# Sheet1.net
KiCad netlist of a schematic drawn in Altium Designer
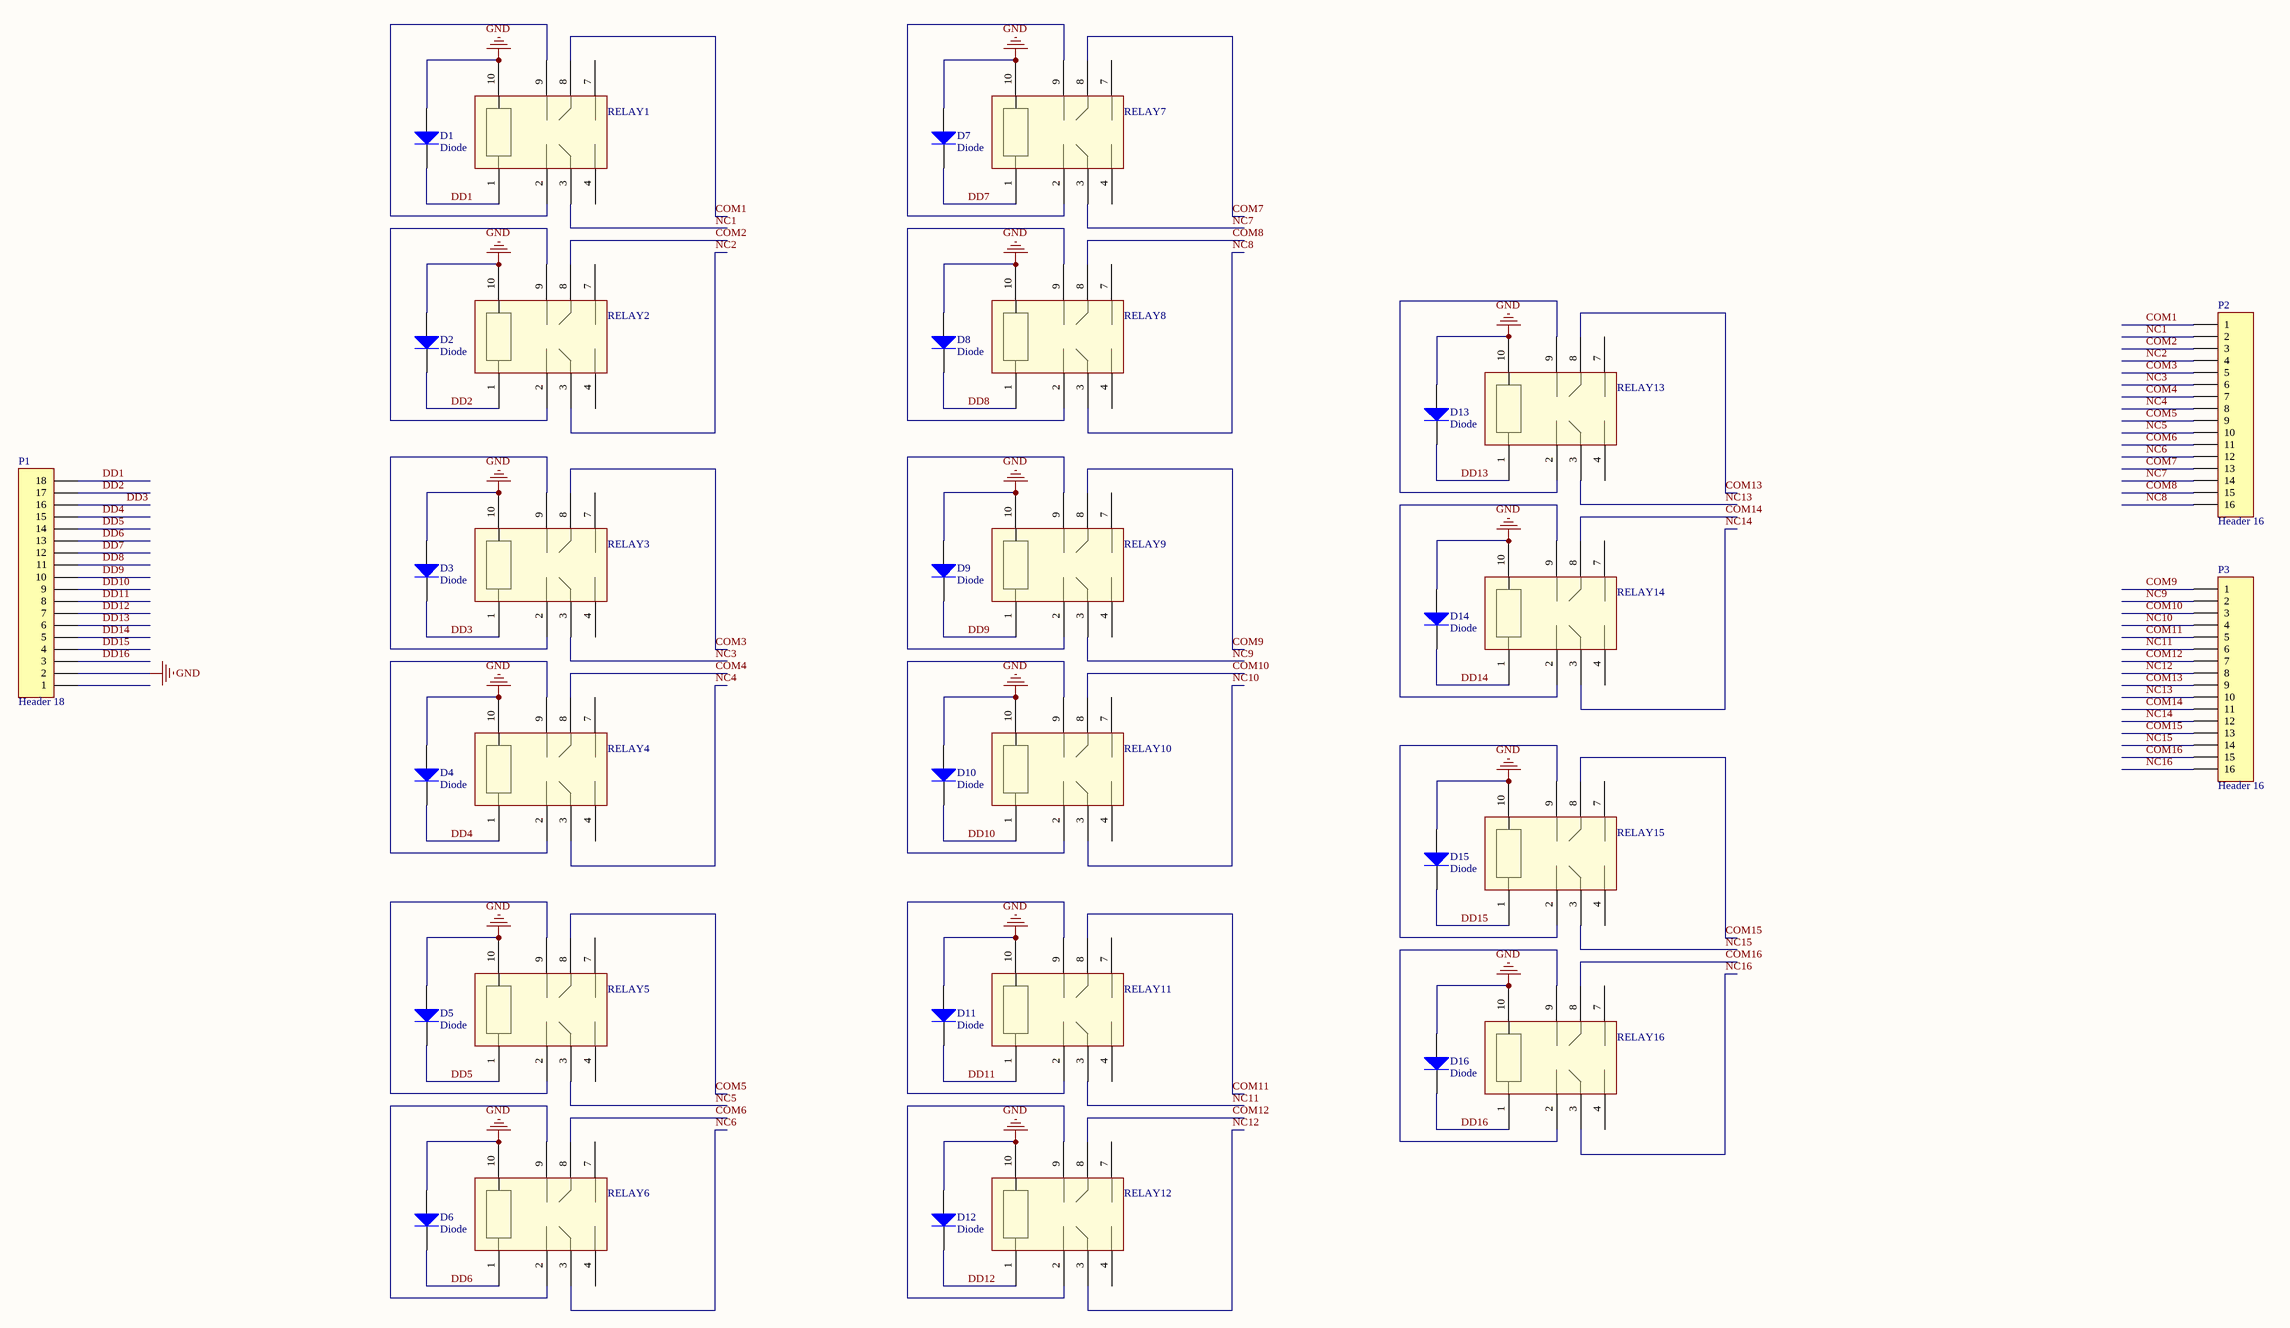
[diagram p0: Sheet1.SchDoc]

(export (version "E")
  (design (tool "Eeschema 10.0.6"))
  (components
    (comp (ref "D1")
      (value "Diode")
      (footprint "SMB")
      (description "Default Diode")
      (fields (field (name "PUBLISHER") "Altium Limited"))
      (libsource (lib "Miscellaneous Devices") (part "Diode"))
    )
    (comp (ref "D2")
      (value "Diode")
      (footprint "SMB")
      (description "Default Diode")
      (fields (field (name "PUBLISHER") "Altium Limited"))
      (libsource (lib "Miscellaneous Devices") (part "Diode"))
    )
    (comp (ref "D3")
      (value "Diode")
      (footprint "SMB")
      (description "Default Diode")
      (fields (field (name "PUBLISHER") "Altium Limited"))
      (libsource (lib "Miscellaneous Devices") (part "Diode"))
    )
    (comp (ref "D4")
      (value "Diode")
      (footprint "SMB")
      (description "Default Diode")
      (fields (field (name "PUBLISHER") "Altium Limited"))
      (libsource (lib "Miscellaneous Devices") (part "Diode"))
    )
    (comp (ref "D5")
      (value "Diode")
      (footprint "SMB")
      (description "Default Diode")
      (fields (field (name "PUBLISHER") "Altium Limited"))
      (libsource (lib "Miscellaneous Devices") (part "Diode"))
    )
    (comp (ref "D6")
      (value "Diode")
      (footprint "SMB")
      (description "Default Diode")
      (fields (field (name "PUBLISHER") "Altium Limited"))
      (libsource (lib "Miscellaneous Devices") (part "Diode"))
    )
    (comp (ref "D7")
      (value "Diode")
      (footprint "SMB")
      (description "Default Diode")
      (fields (field (name "PUBLISHER") "Altium Limited"))
      (libsource (lib "Miscellaneous Devices") (part "Diode"))
    )
    (comp (ref "D8")
      (value "Diode")
      (footprint "SMB")
      (description "Default Diode")
      (fields (field (name "PUBLISHER") "Altium Limited"))
      (libsource (lib "Miscellaneous Devices") (part "Diode"))
    )
    (comp (ref "D9")
      (value "Diode")
      (footprint "SMB")
      (description "Default Diode")
      (fields (field (name "PUBLISHER") "Altium Limited"))
      (libsource (lib "Miscellaneous Devices") (part "Diode"))
    )
    (comp (ref "D10")
      (value "Diode")
      (footprint "SMB")
      (description "Default Diode")
      (fields (field (name "PUBLISHER") "Altium Limited"))
      (libsource (lib "Miscellaneous Devices") (part "Diode"))
    )
    (comp (ref "D11")
      (value "Diode")
      (footprint "SMB")
      (description "Default Diode")
      (fields (field (name "PUBLISHER") "Altium Limited"))
      (libsource (lib "Miscellaneous Devices") (part "Diode"))
    )
    (comp (ref "D12")
      (value "Diode")
      (footprint "SMB")
      (description "Default Diode")
      (fields (field (name "PUBLISHER") "Altium Limited"))
      (libsource (lib "Miscellaneous Devices") (part "Diode"))
    )
    (comp (ref "D13")
      (value "Diode")
      (footprint "SMB")
      (description "Default Diode")
      (fields (field (name "PUBLISHER") "Altium Limited"))
      (libsource (lib "Miscellaneous Devices") (part "Diode"))
    )
    (comp (ref "D14")
      (value "Diode")
      (footprint "SMB")
      (description "Default Diode")
      (fields (field (name "PUBLISHER") "Altium Limited"))
      (libsource (lib "Miscellaneous Devices") (part "Diode"))
    )
    (comp (ref "D15")
      (value "Diode")
      (footprint "SMB")
      (description "Default Diode")
      (fields (field (name "PUBLISHER") "Altium Limited"))
      (libsource (lib "Miscellaneous Devices") (part "Diode"))
    )
    (comp (ref "D16")
      (value "Diode")
      (footprint "SMB")
      (description "Default Diode")
      (fields (field (name "PUBLISHER") "Altium Limited"))
      (libsource (lib "Miscellaneous Devices") (part "Diode"))
    )
    (comp (ref "P1")
      (value "Header 18")
      (footprint "CON 18")
      (description "Header, 18-Pin")
      (fields (field (name "PUBLISHER") "Altium Limited"))
      (libsource (lib "Miscellaneous Connectors") (part "Header 18"))
    )
    (comp (ref "P2")
      (value "Header 16")
      (footprint "CON 16")
      (description "Header, 16-Pin")
      (fields (field (name "PUBLISHER") "Altium Limited"))
      (libsource (lib "Miscellaneous Connectors") (part "Header 16"))
    )
    (comp (ref "P3")
      (value "Header 16")
      (footprint "CON 16")
      (description "Header, 16-Pin")
      (fields (field (name "PUBLISHER") "Altium Limited"))
      (libsource (lib "Miscellaneous Connectors") (part "Header 16"))
    )
    (comp (ref "RELAY1")
      (value "OMRON RELAY")
      (footprint "G6H-2")
      (libsource (lib "dung_maker_2018") (part "OMRON G6H-2"))
    )
    (comp (ref "RELAY2")
      (value "OMRON RELAY")
      (footprint "G6H-2")
      (libsource (lib "dung_maker_2018") (part "OMRON G6H-2"))
    )
    (comp (ref "RELAY3")
      (value "OMRON RELAY")
      (footprint "G6H-2")
      (libsource (lib "dung_maker_2018") (part "OMRON G6H-2"))
    )
    (comp (ref "RELAY4")
      (value "OMRON RELAY")
      (footprint "G6H-2")
      (libsource (lib "dung_maker_2018") (part "OMRON G6H-2"))
    )
    (comp (ref "RELAY5")
      (value "OMRON RELAY")
      (footprint "G6H-2")
      (libsource (lib "dung_maker_2018") (part "OMRON G6H-2"))
    )
    (comp (ref "RELAY6")
      (value "OMRON RELAY")
      (footprint "G6H-2")
      (libsource (lib "dung_maker_2018") (part "OMRON G6H-2"))
    )
    (comp (ref "RELAY7")
      (value "OMRON RELAY")
      (footprint "G6H-2")
      (libsource (lib "dung_maker_2018") (part "OMRON G6H-2"))
    )
    (comp (ref "RELAY8")
      (value "OMRON RELAY")
      (footprint "G6H-2")
      (libsource (lib "dung_maker_2018") (part "OMRON G6H-2"))
    )
    (comp (ref "RELAY9")
      (value "OMRON RELAY")
      (footprint "G6H-2")
      (libsource (lib "dung_maker_2018") (part "OMRON G6H-2"))
    )
    (comp (ref "RELAY10")
      (value "OMRON RELAY")
      (footprint "G6H-2")
      (libsource (lib "dung_maker_2018") (part "OMRON G6H-2"))
    )
    (comp (ref "RELAY11")
      (value "OMRON RELAY")
      (footprint "G6H-2")
      (libsource (lib "dung_maker_2018") (part "OMRON G6H-2"))
    )
    (comp (ref "RELAY12")
      (value "OMRON RELAY")
      (footprint "G6H-2")
      (libsource (lib "dung_maker_2018") (part "OMRON G6H-2"))
    )
    (comp (ref "RELAY13")
      (value "OMRON RELAY")
      (footprint "G6H-2")
      (libsource (lib "dung_maker_2018") (part "OMRON G6H-2"))
    )
    (comp (ref "RELAY14")
      (value "OMRON RELAY")
      (footprint "G6H-2")
      (libsource (lib "dung_maker_2018") (part "OMRON G6H-2"))
    )
    (comp (ref "RELAY15")
      (value "OMRON RELAY")
      (footprint "G6H-2")
      (libsource (lib "dung_maker_2018") (part "OMRON G6H-2"))
    )
    (comp (ref "RELAY16")
      (value "OMRON RELAY")
      (footprint "G6H-2")
      (libsource (lib "dung_maker_2018") (part "OMRON G6H-2"))
    )
  )
  (nets
    (net (code "1") (name "/COM1") (class "Default")
      (node (ref "P2") (pin "1") (pinfunction "1_1") (pintype "passive"))
      (node (ref "RELAY1") (pin "8") (pinfunction "8_8") (pintype "passive"))
    )
    (net (code "2") (name "/COM2") (class "Default")
      (node (ref "P2") (pin "3") (pinfunction "3_3") (pintype "passive"))
      (node (ref "RELAY2") (pin "8") (pinfunction "8_8") (pintype "passive"))
    )
    (net (code "3") (name "/COM3") (class "Default")
      (node (ref "P2") (pin "5") (pinfunction "5_5") (pintype "passive"))
      (node (ref "RELAY3") (pin "8") (pinfunction "8_8") (pintype "passive"))
    )
    (net (code "4") (name "/COM4") (class "Default")
      (node (ref "P2") (pin "7") (pinfunction "7_7") (pintype "passive"))
      (node (ref "RELAY4") (pin "8") (pinfunction "8_8") (pintype "passive"))
    )
    (net (code "5") (name "/COM5") (class "Default")
      (node (ref "P2") (pin "9") (pinfunction "9_9") (pintype "passive"))
      (node (ref "RELAY5") (pin "8") (pinfunction "8_8") (pintype "passive"))
    )
    (net (code "6") (name "/COM6") (class "Default")
      (node (ref "P2") (pin "11") (pinfunction "11_11") (pintype "passive"))
      (node (ref "RELAY6") (pin "8") (pinfunction "8_8") (pintype "passive"))
    )
    (net (code "7") (name "/COM7") (class "Default")
      (node (ref "P2") (pin "13") (pinfunction "13_13") (pintype "passive"))
      (node (ref "RELAY7") (pin "8") (pinfunction "8_8") (pintype "passive"))
    )
    (net (code "8") (name "/COM8") (class "Default")
      (node (ref "P2") (pin "15") (pinfunction "15_15") (pintype "passive"))
      (node (ref "RELAY8") (pin "8") (pinfunction "8_8") (pintype "passive"))
    )
    (net (code "9") (name "/COM9") (class "Default")
      (node (ref "P3") (pin "1") (pinfunction "1_1") (pintype "passive"))
      (node (ref "RELAY9") (pin "8") (pinfunction "8_8") (pintype "passive"))
    )
    (net (code "10") (name "/COM10") (class "Default")
      (node (ref "P3") (pin "3") (pinfunction "3_3") (pintype "passive"))
      (node (ref "RELAY10") (pin "8") (pinfunction "8_8") (pintype "passive"))
    )
    (net (code "11") (name "/COM11") (class "Default")
      (node (ref "P3") (pin "5") (pinfunction "5_5") (pintype "passive"))
      (node (ref "RELAY11") (pin "8") (pinfunction "8_8") (pintype "passive"))
    )
    (net (code "12") (name "/COM12") (class "Default")
      (node (ref "P3") (pin "7") (pinfunction "7_7") (pintype "passive"))
      (node (ref "RELAY12") (pin "8") (pinfunction "8_8") (pintype "passive"))
    )
    (net (code "13") (name "/COM13") (class "Default")
      (node (ref "P3") (pin "9") (pinfunction "9_9") (pintype "passive"))
      (node (ref "RELAY13") (pin "8") (pinfunction "8_8") (pintype "passive"))
    )
    (net (code "14") (name "/COM14") (class "Default")
      (node (ref "P3") (pin "11") (pinfunction "11_11") (pintype "passive"))
      (node (ref "RELAY14") (pin "8") (pinfunction "8_8") (pintype "passive"))
    )
    (net (code "15") (name "/COM15") (class "Default")
      (node (ref "P3") (pin "13") (pinfunction "13_13") (pintype "passive"))
      (node (ref "RELAY15") (pin "8") (pinfunction "8_8") (pintype "passive"))
    )
    (net (code "16") (name "/COM16") (class "Default")
      (node (ref "P3") (pin "15") (pinfunction "15_15") (pintype "passive"))
      (node (ref "RELAY16") (pin "8") (pinfunction "8_8") (pintype "passive"))
    )
    (net (code "17") (name "/DD1") (class "Default")
      (node (ref "D1") (pin "2") (pinfunction "K_2") (pintype "passive"))
      (node (ref "P1") (pin "18") (pinfunction "18_18") (pintype "passive"))
      (node (ref "RELAY1") (pin "1") (pinfunction "1_1") (pintype "passive"))
    )
    (net (code "18") (name "/DD2") (class "Default")
      (node (ref "D2") (pin "2") (pinfunction "K_2") (pintype "passive"))
      (node (ref "P1") (pin "17") (pinfunction "17_17") (pintype "passive"))
      (node (ref "RELAY2") (pin "1") (pinfunction "1_1") (pintype "passive"))
    )
    (net (code "19") (name "/DD3") (class "Default")
      (node (ref "D3") (pin "2") (pinfunction "K_2") (pintype "passive"))
      (node (ref "P1") (pin "16") (pinfunction "16_16") (pintype "passive"))
      (node (ref "RELAY3") (pin "1") (pinfunction "1_1") (pintype "passive"))
    )
    (net (code "20") (name "/DD4") (class "Default")
      (node (ref "D4") (pin "2") (pinfunction "K_2") (pintype "passive"))
      (node (ref "P1") (pin "15") (pinfunction "15_15") (pintype "passive"))
      (node (ref "RELAY4") (pin "1") (pinfunction "1_1") (pintype "passive"))
    )
    (net (code "21") (name "/DD5") (class "Default")
      (node (ref "D5") (pin "2") (pinfunction "K_2") (pintype "passive"))
      (node (ref "P1") (pin "14") (pinfunction "14_14") (pintype "passive"))
      (node (ref "RELAY5") (pin "1") (pinfunction "1_1") (pintype "passive"))
    )
    (net (code "22") (name "/DD6") (class "Default")
      (node (ref "D6") (pin "2") (pinfunction "K_2") (pintype "passive"))
      (node (ref "P1") (pin "13") (pinfunction "13_13") (pintype "passive"))
      (node (ref "RELAY6") (pin "1") (pinfunction "1_1") (pintype "passive"))
    )
    (net (code "23") (name "/DD7") (class "Default")
      (node (ref "D7") (pin "2") (pinfunction "K_2") (pintype "passive"))
      (node (ref "P1") (pin "12") (pinfunction "12_12") (pintype "passive"))
      (node (ref "RELAY7") (pin "1") (pinfunction "1_1") (pintype "passive"))
    )
    (net (code "24") (name "/DD8") (class "Default")
      (node (ref "D8") (pin "2") (pinfunction "K_2") (pintype "passive"))
      (node (ref "P1") (pin "11") (pinfunction "11_11") (pintype "passive"))
      (node (ref "RELAY8") (pin "1") (pinfunction "1_1") (pintype "passive"))
    )
    (net (code "25") (name "/DD9") (class "Default")
      (node (ref "D9") (pin "2") (pinfunction "K_2") (pintype "passive"))
      (node (ref "P1") (pin "10") (pinfunction "10_10") (pintype "passive"))
      (node (ref "RELAY9") (pin "1") (pinfunction "1_1") (pintype "passive"))
    )
    (net (code "26") (name "/DD10") (class "Default")
      (node (ref "D10") (pin "2") (pinfunction "K_2") (pintype "passive"))
      (node (ref "P1") (pin "9") (pinfunction "9_9") (pintype "passive"))
      (node (ref "RELAY10") (pin "1") (pinfunction "1_1") (pintype "passive"))
    )
    (net (code "27") (name "/DD11") (class "Default")
      (node (ref "D11") (pin "2") (pinfunction "K_2") (pintype "passive"))
      (node (ref "P1") (pin "8") (pinfunction "8_8") (pintype "passive"))
      (node (ref "RELAY11") (pin "1") (pinfunction "1_1") (pintype "passive"))
    )
    (net (code "28") (name "/DD12") (class "Default")
      (node (ref "D12") (pin "2") (pinfunction "K_2") (pintype "passive"))
      (node (ref "P1") (pin "7") (pinfunction "7_7") (pintype "passive"))
      (node (ref "RELAY12") (pin "1") (pinfunction "1_1") (pintype "passive"))
    )
    (net (code "29") (name "/DD13") (class "Default")
      (node (ref "D13") (pin "2") (pinfunction "K_2") (pintype "passive"))
      (node (ref "P1") (pin "6") (pinfunction "6_6") (pintype "passive"))
      (node (ref "RELAY13") (pin "1") (pinfunction "1_1") (pintype "passive"))
    )
    (net (code "30") (name "/DD14") (class "Default")
      (node (ref "D14") (pin "2") (pinfunction "K_2") (pintype "passive"))
      (node (ref "P1") (pin "5") (pinfunction "5_5") (pintype "passive"))
      (node (ref "RELAY14") (pin "1") (pinfunction "1_1") (pintype "passive"))
    )
    (net (code "31") (name "/DD15") (class "Default")
      (node (ref "D15") (pin "2") (pinfunction "K_2") (pintype "passive"))
      (node (ref "P1") (pin "4") (pinfunction "4_4") (pintype "passive"))
      (node (ref "RELAY15") (pin "1") (pinfunction "1_1") (pintype "passive"))
    )
    (net (code "32") (name "/DD16") (class "Default")
      (node (ref "D16") (pin "2") (pinfunction "K_2") (pintype "passive"))
      (node (ref "P1") (pin "3") (pinfunction "3_3") (pintype "passive"))
      (node (ref "RELAY16") (pin "1") (pinfunction "1_1") (pintype "passive"))
    )
    (net (code "33") (name "/NC1") (class "Default")
      (node (ref "P2") (pin "2") (pinfunction "2_2") (pintype "passive"))
      (node (ref "RELAY1") (pin "3") (pinfunction "3_3") (pintype "passive"))
    )
    (net (code "34") (name "/NC2") (class "Default")
      (node (ref "P2") (pin "4") (pinfunction "4_4") (pintype "passive"))
      (node (ref "RELAY2") (pin "3") (pinfunction "3_3") (pintype "passive"))
    )
    (net (code "35") (name "/NC3") (class "Default")
      (node (ref "P2") (pin "6") (pinfunction "6_6") (pintype "passive"))
      (node (ref "RELAY3") (pin "3") (pinfunction "3_3") (pintype "passive"))
    )
    (net (code "36") (name "/NC4") (class "Default")
      (node (ref "P2") (pin "8") (pinfunction "8_8") (pintype "passive"))
      (node (ref "RELAY4") (pin "3") (pinfunction "3_3") (pintype "passive"))
    )
    (net (code "37") (name "/NC5") (class "Default")
      (node (ref "P2") (pin "10") (pinfunction "10_10") (pintype "passive"))
      (node (ref "RELAY5") (pin "3") (pinfunction "3_3") (pintype "passive"))
    )
    (net (code "38") (name "/NC6") (class "Default")
      (node (ref "P2") (pin "12") (pinfunction "12_12") (pintype "passive"))
      (node (ref "RELAY6") (pin "3") (pinfunction "3_3") (pintype "passive"))
    )
    (net (code "39") (name "/NC7") (class "Default")
      (node (ref "P2") (pin "14") (pinfunction "14_14") (pintype "passive"))
      (node (ref "RELAY7") (pin "3") (pinfunction "3_3") (pintype "passive"))
    )
    (net (code "40") (name "/NC8") (class "Default")
      (node (ref "P2") (pin "16") (pinfunction "16_16") (pintype "passive"))
      (node (ref "RELAY8") (pin "3") (pinfunction "3_3") (pintype "passive"))
    )
    (net (code "41") (name "/NC9") (class "Default")
      (node (ref "P3") (pin "2") (pinfunction "2_2") (pintype "passive"))
      (node (ref "RELAY9") (pin "3") (pinfunction "3_3") (pintype "passive"))
    )
    (net (code "42") (name "/NC10") (class "Default")
      (node (ref "P3") (pin "4") (pinfunction "4_4") (pintype "passive"))
      (node (ref "RELAY10") (pin "3") (pinfunction "3_3") (pintype "passive"))
    )
    (net (code "43") (name "/NC11") (class "Default")
      (node (ref "P3") (pin "6") (pinfunction "6_6") (pintype "passive"))
      (node (ref "RELAY11") (pin "3") (pinfunction "3_3") (pintype "passive"))
    )
    (net (code "44") (name "/NC12") (class "Default")
      (node (ref "P3") (pin "8") (pinfunction "8_8") (pintype "passive"))
      (node (ref "RELAY12") (pin "3") (pinfunction "3_3") (pintype "passive"))
    )
    (net (code "45") (name "/NC13") (class "Default")
      (node (ref "P3") (pin "10") (pinfunction "10_10") (pintype "passive"))
      (node (ref "RELAY13") (pin "3") (pinfunction "3_3") (pintype "passive"))
    )
    (net (code "46") (name "/NC14") (class "Default")
      (node (ref "P3") (pin "12") (pinfunction "12_12") (pintype "passive"))
      (node (ref "RELAY14") (pin "3") (pinfunction "3_3") (pintype "passive"))
    )
    (net (code "47") (name "/NC15") (class "Default")
      (node (ref "P3") (pin "14") (pinfunction "14_14") (pintype "passive"))
      (node (ref "RELAY15") (pin "3") (pinfunction "3_3") (pintype "passive"))
    )
    (net (code "48") (name "/NC16") (class "Default")
      (node (ref "P3") (pin "16") (pinfunction "16_16") (pintype "passive"))
      (node (ref "RELAY16") (pin "3") (pinfunction "3_3") (pintype "passive"))
    )
    (net (code "49") (name "GND") (class "Default")
      (node (ref "D1") (pin "1") (pinfunction "A_1") (pintype "passive"))
      (node (ref "D10") (pin "1") (pinfunction "A_1") (pintype "passive"))
      (node (ref "D11") (pin "1") (pinfunction "A_1") (pintype "passive"))
      (node (ref "D12") (pin "1") (pinfunction "A_1") (pintype "passive"))
      (node (ref "D13") (pin "1") (pinfunction "A_1") (pintype "passive"))
      (node (ref "D14") (pin "1") (pinfunction "A_1") (pintype "passive"))
      (node (ref "D15") (pin "1") (pinfunction "A_1") (pintype "passive"))
      (node (ref "D16") (pin "1") (pinfunction "A_1") (pintype "passive"))
      (node (ref "D2") (pin "1") (pinfunction "A_1") (pintype "passive"))
      (node (ref "D3") (pin "1") (pinfunction "A_1") (pintype "passive"))
      (node (ref "D4") (pin "1") (pinfunction "A_1") (pintype "passive"))
      (node (ref "D5") (pin "1") (pinfunction "A_1") (pintype "passive"))
      (node (ref "D6") (pin "1") (pinfunction "A_1") (pintype "passive"))
      (node (ref "D7") (pin "1") (pinfunction "A_1") (pintype "passive"))
      (node (ref "D8") (pin "1") (pinfunction "A_1") (pintype "passive"))
      (node (ref "D9") (pin "1") (pinfunction "A_1") (pintype "passive"))
      (node (ref "P1") (pin "2") (pinfunction "2_2") (pintype "passive"))
      (node (ref "RELAY1") (pin "10") (pinfunction "10_10") (pintype "passive"))
      (node (ref "RELAY10") (pin "10") (pinfunction "10_10") (pintype "passive"))
      (node (ref "RELAY11") (pin "10") (pinfunction "10_10") (pintype "passive"))
      (node (ref "RELAY12") (pin "10") (pinfunction "10_10") (pintype "passive"))
      (node (ref "RELAY13") (pin "10") (pinfunction "10_10") (pintype "passive"))
      (node (ref "RELAY14") (pin "10") (pinfunction "10_10") (pintype "passive"))
      (node (ref "RELAY15") (pin "10") (pinfunction "10_10") (pintype "passive"))
      (node (ref "RELAY16") (pin "10") (pinfunction "10_10") (pintype "passive"))
      (node (ref "RELAY2") (pin "10") (pinfunction "10_10") (pintype "passive"))
      (node (ref "RELAY3") (pin "10") (pinfunction "10_10") (pintype "passive"))
      (node (ref "RELAY4") (pin "10") (pinfunction "10_10") (pintype "passive"))
      (node (ref "RELAY5") (pin "10") (pinfunction "10_10") (pintype "passive"))
      (node (ref "RELAY6") (pin "10") (pinfunction "10_10") (pintype "passive"))
      (node (ref "RELAY7") (pin "10") (pinfunction "10_10") (pintype "passive"))
      (node (ref "RELAY8") (pin "10") (pinfunction "10_10") (pintype "passive"))
      (node (ref "RELAY9") (pin "10") (pinfunction "10_10") (pintype "passive"))
    )
    (net (code "50") (name "Net-(RELAY1-Pad2)") (class "Default")
      (node (ref "RELAY1") (pin "2") (pinfunction "2_2") (pintype "passive"))
      (node (ref "RELAY1") (pin "9") (pinfunction "9_9") (pintype "passive"))
    )
    (net (code "51") (name "Net-(RELAY2-Pad2)") (class "Default")
      (node (ref "RELAY2") (pin "2") (pinfunction "2_2") (pintype "passive"))
      (node (ref "RELAY2") (pin "9") (pinfunction "9_9") (pintype "passive"))
    )
    (net (code "52") (name "Net-(RELAY3-Pad2)") (class "Default")
      (node (ref "RELAY3") (pin "2") (pinfunction "2_2") (pintype "passive"))
      (node (ref "RELAY3") (pin "9") (pinfunction "9_9") (pintype "passive"))
    )
    (net (code "53") (name "Net-(RELAY4-Pad2)") (class "Default")
      (node (ref "RELAY4") (pin "2") (pinfunction "2_2") (pintype "passive"))
      (node (ref "RELAY4") (pin "9") (pinfunction "9_9") (pintype "passive"))
    )
    (net (code "54") (name "Net-(RELAY5-Pad2)") (class "Default")
      (node (ref "RELAY5") (pin "2") (pinfunction "2_2") (pintype "passive"))
      (node (ref "RELAY5") (pin "9") (pinfunction "9_9") (pintype "passive"))
    )
    (net (code "55") (name "Net-(RELAY6-Pad2)") (class "Default")
      (node (ref "RELAY6") (pin "2") (pinfunction "2_2") (pintype "passive"))
      (node (ref "RELAY6") (pin "9") (pinfunction "9_9") (pintype "passive"))
    )
    (net (code "56") (name "Net-(RELAY7-Pad2)") (class "Default")
      (node (ref "RELAY7") (pin "2") (pinfunction "2_2") (pintype "passive"))
      (node (ref "RELAY7") (pin "9") (pinfunction "9_9") (pintype "passive"))
    )
    (net (code "57") (name "Net-(RELAY8-Pad2)") (class "Default")
      (node (ref "RELAY8") (pin "2") (pinfunction "2_2") (pintype "passive"))
      (node (ref "RELAY8") (pin "9") (pinfunction "9_9") (pintype "passive"))
    )
    (net (code "58") (name "Net-(RELAY9-Pad2)") (class "Default")
      (node (ref "RELAY9") (pin "2") (pinfunction "2_2") (pintype "passive"))
      (node (ref "RELAY9") (pin "9") (pinfunction "9_9") (pintype "passive"))
    )
    (net (code "59") (name "Net-(RELAY10-Pad2)") (class "Default")
      (node (ref "RELAY10") (pin "2") (pinfunction "2_2") (pintype "passive"))
      (node (ref "RELAY10") (pin "9") (pinfunction "9_9") (pintype "passive"))
    )
    (net (code "60") (name "Net-(RELAY11-Pad2)") (class "Default")
      (node (ref "RELAY11") (pin "2") (pinfunction "2_2") (pintype "passive"))
      (node (ref "RELAY11") (pin "9") (pinfunction "9_9") (pintype "passive"))
    )
    (net (code "61") (name "Net-(RELAY12-Pad2)") (class "Default")
      (node (ref "RELAY12") (pin "2") (pinfunction "2_2") (pintype "passive"))
      (node (ref "RELAY12") (pin "9") (pinfunction "9_9") (pintype "passive"))
    )
    (net (code "62") (name "Net-(RELAY13-Pad2)") (class "Default")
      (node (ref "RELAY13") (pin "2") (pinfunction "2_2") (pintype "passive"))
      (node (ref "RELAY13") (pin "9") (pinfunction "9_9") (pintype "passive"))
    )
    (net (code "63") (name "Net-(RELAY14-Pad2)") (class "Default")
      (node (ref "RELAY14") (pin "2") (pinfunction "2_2") (pintype "passive"))
      (node (ref "RELAY14") (pin "9") (pinfunction "9_9") (pintype "passive"))
    )
    (net (code "64") (name "Net-(RELAY15-Pad2)") (class "Default")
      (node (ref "RELAY15") (pin "2") (pinfunction "2_2") (pintype "passive"))
      (node (ref "RELAY15") (pin "9") (pinfunction "9_9") (pintype "passive"))
    )
    (net (code "65") (name "Net-(RELAY16-Pad2)") (class "Default")
      (node (ref "RELAY16") (pin "2") (pinfunction "2_2") (pintype "passive"))
      (node (ref "RELAY16") (pin "9") (pinfunction "9_9") (pintype "passive"))
    )
    (net (code "66") (name "unconnected-(P1-Pad1)") (class "Default")
      (node (ref "P1") (pin "1") (pinfunction "1_1") (pintype "passive"))
    )
    (net (code "67") (name "unconnected-(RELAY1-Pad4)") (class "Default")
      (node (ref "RELAY1") (pin "4") (pinfunction "4_4") (pintype "passive"))
    )
    (net (code "68") (name "unconnected-(RELAY1-Pad5)") (class "Default")
      (node (ref "RELAY1") (pin "5") (pinfunction "5_5") (pintype "passive"))
    )
    (net (code "69") (name "unconnected-(RELAY1-Pad6)") (class "Default")
      (node (ref "RELAY1") (pin "6") (pinfunction "6_6") (pintype "passive"))
    )
    (net (code "70") (name "unconnected-(RELAY1-Pad7)") (class "Default")
      (node (ref "RELAY1") (pin "7") (pinfunction "7_7") (pintype "passive"))
    )
    (net (code "71") (name "unconnected-(RELAY2-Pad4)") (class "Default")
      (node (ref "RELAY2") (pin "4") (pinfunction "4_4") (pintype "passive"))
    )
    (net (code "72") (name "unconnected-(RELAY2-Pad5)") (class "Default")
      (node (ref "RELAY2") (pin "5") (pinfunction "5_5") (pintype "passive"))
    )
    (net (code "73") (name "unconnected-(RELAY2-Pad6)") (class "Default")
      (node (ref "RELAY2") (pin "6") (pinfunction "6_6") (pintype "passive"))
    )
    (net (code "74") (name "unconnected-(RELAY2-Pad7)") (class "Default")
      (node (ref "RELAY2") (pin "7") (pinfunction "7_7") (pintype "passive"))
    )
    (net (code "75") (name "unconnected-(RELAY3-Pad4)") (class "Default")
      (node (ref "RELAY3") (pin "4") (pinfunction "4_4") (pintype "passive"))
    )
    (net (code "76") (name "unconnected-(RELAY3-Pad5)") (class "Default")
      (node (ref "RELAY3") (pin "5") (pinfunction "5_5") (pintype "passive"))
    )
    (net (code "77") (name "unconnected-(RELAY3-Pad6)") (class "Default")
      (node (ref "RELAY3") (pin "6") (pinfunction "6_6") (pintype "passive"))
    )
    (net (code "78") (name "unconnected-(RELAY3-Pad7)") (class "Default")
      (node (ref "RELAY3") (pin "7") (pinfunction "7_7") (pintype "passive"))
    )
    (net (code "79") (name "unconnected-(RELAY4-Pad4)") (class "Default")
      (node (ref "RELAY4") (pin "4") (pinfunction "4_4") (pintype "passive"))
    )
    (net (code "80") (name "unconnected-(RELAY4-Pad5)") (class "Default")
      (node (ref "RELAY4") (pin "5") (pinfunction "5_5") (pintype "passive"))
    )
    (net (code "81") (name "unconnected-(RELAY4-Pad6)") (class "Default")
      (node (ref "RELAY4") (pin "6") (pinfunction "6_6") (pintype "passive"))
    )
    (net (code "82") (name "unconnected-(RELAY4-Pad7)") (class "Default")
      (node (ref "RELAY4") (pin "7") (pinfunction "7_7") (pintype "passive"))
    )
    (net (code "83") (name "unconnected-(RELAY5-Pad4)") (class "Default")
      (node (ref "RELAY5") (pin "4") (pinfunction "4_4") (pintype "passive"))
    )
    (net (code "84") (name "unconnected-(RELAY5-Pad5)") (class "Default")
      (node (ref "RELAY5") (pin "5") (pinfunction "5_5") (pintype "passive"))
    )
    (net (code "85") (name "unconnected-(RELAY5-Pad6)") (class "Default")
      (node (ref "RELAY5") (pin "6") (pinfunction "6_6") (pintype "passive"))
    )
    (net (code "86") (name "unconnected-(RELAY5-Pad7)") (class "Default")
      (node (ref "RELAY5") (pin "7") (pinfunction "7_7") (pintype "passive"))
    )
    (net (code "87") (name "unconnected-(RELAY6-Pad4)") (class "Default")
      (node (ref "RELAY6") (pin "4") (pinfunction "4_4") (pintype "passive"))
    )
    (net (code "88") (name "unconnected-(RELAY6-Pad5)") (class "Default")
      (node (ref "RELAY6") (pin "5") (pinfunction "5_5") (pintype "passive"))
    )
    (net (code "89") (name "unconnected-(RELAY6-Pad6)") (class "Default")
      (node (ref "RELAY6") (pin "6") (pinfunction "6_6") (pintype "passive"))
    )
    (net (code "90") (name "unconnected-(RELAY6-Pad7)") (class "Default")
      (node (ref "RELAY6") (pin "7") (pinfunction "7_7") (pintype "passive"))
    )
    (net (code "91") (name "unconnected-(RELAY7-Pad4)") (class "Default")
      (node (ref "RELAY7") (pin "4") (pinfunction "4_4") (pintype "passive"))
    )
    (net (code "92") (name "unconnected-(RELAY7-Pad5)") (class "Default")
      (node (ref "RELAY7") (pin "5") (pinfunction "5_5") (pintype "passive"))
    )
    (net (code "93") (name "unconnected-(RELAY7-Pad6)") (class "Default")
      (node (ref "RELAY7") (pin "6") (pinfunction "6_6") (pintype "passive"))
    )
    (net (code "94") (name "unconnected-(RELAY7-Pad7)") (class "Default")
      (node (ref "RELAY7") (pin "7") (pinfunction "7_7") (pintype "passive"))
    )
    (net (code "95") (name "unconnected-(RELAY8-Pad4)") (class "Default")
      (node (ref "RELAY8") (pin "4") (pinfunction "4_4") (pintype "passive"))
    )
    (net (code "96") (name "unconnected-(RELAY8-Pad5)") (class "Default")
      (node (ref "RELAY8") (pin "5") (pinfunction "5_5") (pintype "passive"))
    )
    (net (code "97") (name "unconnected-(RELAY8-Pad6)") (class "Default")
      (node (ref "RELAY8") (pin "6") (pinfunction "6_6") (pintype "passive"))
    )
    (net (code "98") (name "unconnected-(RELAY8-Pad7)") (class "Default")
      (node (ref "RELAY8") (pin "7") (pinfunction "7_7") (pintype "passive"))
    )
    (net (code "99") (name "unconnected-(RELAY9-Pad4)") (class "Default")
      (node (ref "RELAY9") (pin "4") (pinfunction "4_4") (pintype "passive"))
    )
    (net (code "100") (name "unconnected-(RELAY9-Pad5)") (class "Default")
      (node (ref "RELAY9") (pin "5") (pinfunction "5_5") (pintype "passive"))
    )
    (net (code "101") (name "unconnected-(RELAY9-Pad6)") (class "Default")
      (node (ref "RELAY9") (pin "6") (pinfunction "6_6") (pintype "passive"))
    )
    (net (code "102") (name "unconnected-(RELAY9-Pad7)") (class "Default")
      (node (ref "RELAY9") (pin "7") (pinfunction "7_7") (pintype "passive"))
    )
    (net (code "103") (name "unconnected-(RELAY10-Pad4)") (class "Default")
      (node (ref "RELAY10") (pin "4") (pinfunction "4_4") (pintype "passive"))
    )
    (net (code "104") (name "unconnected-(RELAY10-Pad5)") (class "Default")
      (node (ref "RELAY10") (pin "5") (pinfunction "5_5") (pintype "passive"))
    )
    (net (code "105") (name "unconnected-(RELAY10-Pad6)") (class "Default")
      (node (ref "RELAY10") (pin "6") (pinfunction "6_6") (pintype "passive"))
    )
    (net (code "106") (name "unconnected-(RELAY10-Pad7)") (class "Default")
      (node (ref "RELAY10") (pin "7") (pinfunction "7_7") (pintype "passive"))
    )
    (net (code "107") (name "unconnected-(RELAY11-Pad4)") (class "Default")
      (node (ref "RELAY11") (pin "4") (pinfunction "4_4") (pintype "passive"))
    )
    (net (code "108") (name "unconnected-(RELAY11-Pad5)") (class "Default")
      (node (ref "RELAY11") (pin "5") (pinfunction "5_5") (pintype "passive"))
    )
    (net (code "109") (name "unconnected-(RELAY11-Pad6)") (class "Default")
      (node (ref "RELAY11") (pin "6") (pinfunction "6_6") (pintype "passive"))
    )
    (net (code "110") (name "unconnected-(RELAY11-Pad7)") (class "Default")
      (node (ref "RELAY11") (pin "7") (pinfunction "7_7") (pintype "passive"))
    )
    (net (code "111") (name "unconnected-(RELAY12-Pad4)") (class "Default")
      (node (ref "RELAY12") (pin "4") (pinfunction "4_4") (pintype "passive"))
    )
    (net (code "112") (name "unconnected-(RELAY12-Pad5)") (class "Default")
      (node (ref "RELAY12") (pin "5") (pinfunction "5_5") (pintype "passive"))
    )
    (net (code "113") (name "unconnected-(RELAY12-Pad6)") (class "Default")
      (node (ref "RELAY12") (pin "6") (pinfunction "6_6") (pintype "passive"))
    )
    (net (code "114") (name "unconnected-(RELAY12-Pad7)") (class "Default")
      (node (ref "RELAY12") (pin "7") (pinfunction "7_7") (pintype "passive"))
    )
    (net (code "115") (name "unconnected-(RELAY13-Pad4)") (class "Default")
      (node (ref "RELAY13") (pin "4") (pinfunction "4_4") (pintype "passive"))
    )
    (net (code "116") (name "unconnected-(RELAY13-Pad5)") (class "Default")
      (node (ref "RELAY13") (pin "5") (pinfunction "5_5") (pintype "passive"))
    )
    (net (code "117") (name "unconnected-(RELAY13-Pad6)") (class "Default")
      (node (ref "RELAY13") (pin "6") (pinfunction "6_6") (pintype "passive"))
    )
    (net (code "118") (name "unconnected-(RELAY13-Pad7)") (class "Default")
      (node (ref "RELAY13") (pin "7") (pinfunction "7_7") (pintype "passive"))
    )
    (net (code "119") (name "unconnected-(RELAY14-Pad4)") (class "Default")
      (node (ref "RELAY14") (pin "4") (pinfunction "4_4") (pintype "passive"))
    )
    (net (code "120") (name "unconnected-(RELAY14-Pad5)") (class "Default")
      (node (ref "RELAY14") (pin "5") (pinfunction "5_5") (pintype "passive"))
    )
    (net (code "121") (name "unconnected-(RELAY14-Pad6)") (class "Default")
      (node (ref "RELAY14") (pin "6") (pinfunction "6_6") (pintype "passive"))
    )
    (net (code "122") (name "unconnected-(RELAY14-Pad7)") (class "Default")
      (node (ref "RELAY14") (pin "7") (pinfunction "7_7") (pintype "passive"))
    )
    (net (code "123") (name "unconnected-(RELAY15-Pad4)") (class "Default")
      (node (ref "RELAY15") (pin "4") (pinfunction "4_4") (pintype "passive"))
    )
    (net (code "124") (name "unconnected-(RELAY15-Pad5)") (class "Default")
      (node (ref "RELAY15") (pin "5") (pinfunction "5_5") (pintype "passive"))
    )
    (net (code "125") (name "unconnected-(RELAY15-Pad6)") (class "Default")
      (node (ref "RELAY15") (pin "6") (pinfunction "6_6") (pintype "passive"))
    )
    (net (code "126") (name "unconnected-(RELAY15-Pad7)") (class "Default")
      (node (ref "RELAY15") (pin "7") (pinfunction "7_7") (pintype "passive"))
    )
    (net (code "127") (name "unconnected-(RELAY16-Pad4)") (class "Default")
      (node (ref "RELAY16") (pin "4") (pinfunction "4_4") (pintype "passive"))
    )
    (net (code "128") (name "unconnected-(RELAY16-Pad5)") (class "Default")
      (node (ref "RELAY16") (pin "5") (pinfunction "5_5") (pintype "passive"))
    )
    (net (code "129") (name "unconnected-(RELAY16-Pad6)") (class "Default")
      (node (ref "RELAY16") (pin "6") (pinfunction "6_6") (pintype "passive"))
    )
    (net (code "130") (name "unconnected-(RELAY16-Pad7)") (class "Default")
      (node (ref "RELAY16") (pin "7") (pinfunction "7_7") (pintype "passive"))
    )
  )
)
